# siso.net
KiCad netlist of a schematic drawn in EAGLE
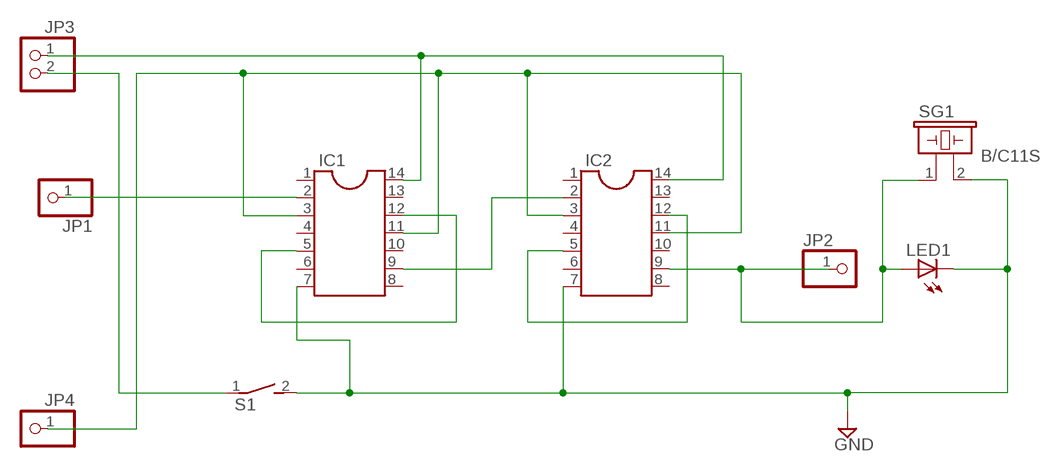
[diagram p0: schematic, sheet 1]

(export (version "E")
  (design (tool "Eeschema 10.0.6"))
  (components
    (comp (ref "IC1")
      (value "DIL14")
      (footprint "eagle-import:DIL14")
      (libsource (lib "eagle-import") (part "DIL14"))
    )
    (comp (ref "IC2")
      (value "DIL14")
      (footprint "eagle-import:DIL14")
      (libsource (lib "eagle-import") (part "DIL14"))
    )
    (comp (ref "JP1")
      (value "PINHD-1X1")
      (footprint "eagle-import:1X01")
      (libsource (lib "eagle-import") (part "PINHD-1X1"))
    )
    (comp (ref "JP2")
      (value "PINHD-1X1")
      (footprint "eagle-import:1X01")
      (libsource (lib "eagle-import") (part "PINHD-1X1"))
    )
    (comp (ref "JP3")
      (value "PINHD-1X2")
      (footprint "eagle-import:1X02")
      (libsource (lib "eagle-import") (part "PINHD-1X2"))
    )
    (comp (ref "JP4")
      (value "PINHD-1X1")
      (footprint "eagle-import:1X01")
      (libsource (lib "eagle-import") (part "PINHD-1X1"))
    )
    (comp (ref "LED1")
      (value "LED5MM")
      (footprint "eagle-import:LED5MM")
      (libsource (lib "eagle-import") (part "LED5MM"))
    )
    (comp (ref "S1")
      (value "DS01E")
      (footprint "eagle-import:DS-01")
      (libsource (lib "eagle-import") (part "DS01E"))
    )
    (comp (ref "SG1")
      (value "B/C11S")
      (footprint "eagle-import:B_C11S")
      (libsource (lib "eagle-import") (part "B/C11S"))
    )
  )
  (nets
    (net (code "1") (name "GND") (class "Default")
      (node (ref "IC1") (pin "7") (pinfunction "7_7") (pintype "passive"))
      (node (ref "IC2") (pin "7") (pinfunction "7_7") (pintype "passive"))
      (node (ref "LED1") (pin "K") (pinfunction "C_K") (pintype "passive"))
      (node (ref "S1") (pin "2") (pinfunction "2_2") (pintype "passive"))
      (node (ref "SG1") (pin "2") (pinfunction "2_2") (pintype "passive"))
    )
    (net (code "2") (name "Net-(IC1-Pad2)") (class "Default")
      (node (ref "IC1") (pin "2") (pinfunction "2_2") (pintype "passive"))
      (node (ref "JP1") (pin "1") (pinfunction "1_1") (pintype "passive"))
    )
    (net (code "3") (name "Net-(IC1-Pad9)") (class "Default")
      (node (ref "IC1") (pin "9") (pinfunction "9_9") (pintype "passive"))
      (node (ref "IC2") (pin "2") (pinfunction "2_2") (pintype "passive"))
    )
    (net (code "4") (name "Net-(IC1-Pad11)") (class "Default")
      (node (ref "IC1") (pin "11") (pinfunction "11_11") (pintype "passive"))
      (node (ref "IC1") (pin "3") (pinfunction "3_3") (pintype "passive"))
      (node (ref "IC2") (pin "11") (pinfunction "11_11") (pintype "passive"))
      (node (ref "IC2") (pin "3") (pinfunction "3_3") (pintype "passive"))
      (node (ref "JP4") (pin "1") (pinfunction "1_1") (pintype "passive"))
    )
    (net (code "5") (name "Net-(IC1-Pad12)") (class "Default")
      (node (ref "IC1") (pin "12") (pinfunction "12_12") (pintype "passive"))
      (node (ref "IC1") (pin "5") (pinfunction "5_5") (pintype "passive"))
    )
    (net (code "6") (name "Net-(IC1-Pad14)") (class "Default")
      (node (ref "IC1") (pin "14") (pinfunction "14_14") (pintype "passive"))
      (node (ref "IC2") (pin "14") (pinfunction "14_14") (pintype "passive"))
      (node (ref "JP3") (pin "1") (pinfunction "1_1") (pintype "passive"))
    )
    (net (code "7") (name "Net-(IC2-Pad9)") (class "Default")
      (node (ref "IC2") (pin "9") (pinfunction "9_9") (pintype "passive"))
      (node (ref "JP2") (pin "1") (pinfunction "1_1") (pintype "passive"))
      (node (ref "LED1") (pin "A") (pinfunction "A_A") (pintype "passive"))
      (node (ref "SG1") (pin "1") (pinfunction "1_1") (pintype "passive"))
    )
    (net (code "8") (name "Net-(IC2-Pad12)") (class "Default")
      (node (ref "IC2") (pin "12") (pinfunction "12_12") (pintype "passive"))
      (node (ref "IC2") (pin "5") (pinfunction "5_5") (pintype "passive"))
    )
    (net (code "9") (name "Net-(JP3-Pad2)") (class "Default")
      (node (ref "JP3") (pin "2") (pinfunction "2_2") (pintype "passive"))
      (node (ref "S1") (pin "1") (pinfunction "1_1") (pintype "passive"))
    )
    (net (code "10") (name "unconnected-(IC1-Pad1)") (class "Default")
      (node (ref "IC1") (pin "1") (pinfunction "1_1") (pintype "passive"))
    )
    (net (code "11") (name "unconnected-(IC1-Pad4)") (class "Default")
      (node (ref "IC1") (pin "4") (pinfunction "4_4") (pintype "passive"))
    )
    (net (code "12") (name "unconnected-(IC1-Pad6)") (class "Default")
      (node (ref "IC1") (pin "6") (pinfunction "6_6") (pintype "passive"))
    )
    (net (code "13") (name "unconnected-(IC1-Pad8)") (class "Default")
      (node (ref "IC1") (pin "8") (pinfunction "8_8") (pintype "passive"))
    )
    (net (code "14") (name "unconnected-(IC1-Pad10)") (class "Default")
      (node (ref "IC1") (pin "10") (pinfunction "10_10") (pintype "passive"))
    )
    (net (code "15") (name "unconnected-(IC1-Pad13)") (class "Default")
      (node (ref "IC1") (pin "13") (pinfunction "13_13") (pintype "passive"))
    )
    (net (code "16") (name "unconnected-(IC2-Pad1)") (class "Default")
      (node (ref "IC2") (pin "1") (pinfunction "1_1") (pintype "passive"))
    )
    (net (code "17") (name "unconnected-(IC2-Pad4)") (class "Default")
      (node (ref "IC2") (pin "4") (pinfunction "4_4") (pintype "passive"))
    )
    (net (code "18") (name "unconnected-(IC2-Pad6)") (class "Default")
      (node (ref "IC2") (pin "6") (pinfunction "6_6") (pintype "passive"))
    )
    (net (code "19") (name "unconnected-(IC2-Pad8)") (class "Default")
      (node (ref "IC2") (pin "8") (pinfunction "8_8") (pintype "passive"))
    )
    (net (code "20") (name "unconnected-(IC2-Pad10)") (class "Default")
      (node (ref "IC2") (pin "10") (pinfunction "10_10") (pintype "passive"))
    )
    (net (code "21") (name "unconnected-(IC2-Pad13)") (class "Default")
      (node (ref "IC2") (pin "13") (pinfunction "13_13") (pintype "passive"))
    )
  )
)
